# FINAL_MMBoard.net
KiCad netlist of a schematic drawn in EAGLE
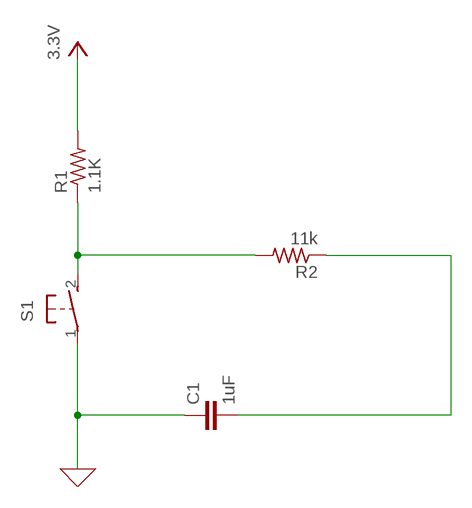
[diagram p0: schematic, sheet 1]

(export (version "E")
  (design (tool "Eeschema 10.0.6"))
  (components
    (comp (ref "C1")
      (value "1uF")
      (footprint "eagle-import:C2.5-3")
      (libsource (lib "eagle-import") (part "C2,5-3"))
    )
    (comp (ref "R1")
      (value "1.1K")
      (footprint "eagle-import:0204V")
      (libsource (lib "eagle-import") (part "R-US_0204/2V"))
    )
    (comp (ref "R2")
      (value "11k")
      (footprint "eagle-import:0204V")
      (libsource (lib "eagle-import") (part "R-US_0204/2V"))
    )
    (comp (ref "S1")
      (value "31-XX")
      (footprint "eagle-import:B3F-31XX")
      (fields (field (name "MPN") "B3F-3100"))
      (libsource (lib "eagle-import") (part "31-XX"))
    )
  )
  (nets
    (net (code "1") (name "3.3V") (class "Default")
      (node (ref "R1") (pin "2") (pinfunction "2_2") (pintype "passive"))
    )
    (net (code "2") (name "GND") (class "Default")
      (node (ref "C1") (pin "1") (pinfunction "1_1") (pintype "passive"))
      (node (ref "S1") (pin "1") (pinfunction "P_1") (pintype "passive"))
    )
    (net (code "3") (name "Net-(C1-Pad2)") (class "Default")
      (node (ref "C1") (pin "2") (pinfunction "2_2") (pintype "passive"))
      (node (ref "R2") (pin "1") (pinfunction "1_1") (pintype "passive"))
    )
    (net (code "4") (name "Net-(S1-S)") (class "Default")
      (node (ref "R1") (pin "1") (pinfunction "1_1") (pintype "passive"))
      (node (ref "R2") (pin "2") (pinfunction "2_2") (pintype "passive"))
      (node (ref "S1") (pin "2") (pinfunction "S_2") (pintype "passive"))
    )
  )
)
